# ArduinixMOD.net
KiCad netlist of a schematic drawn in EAGLE
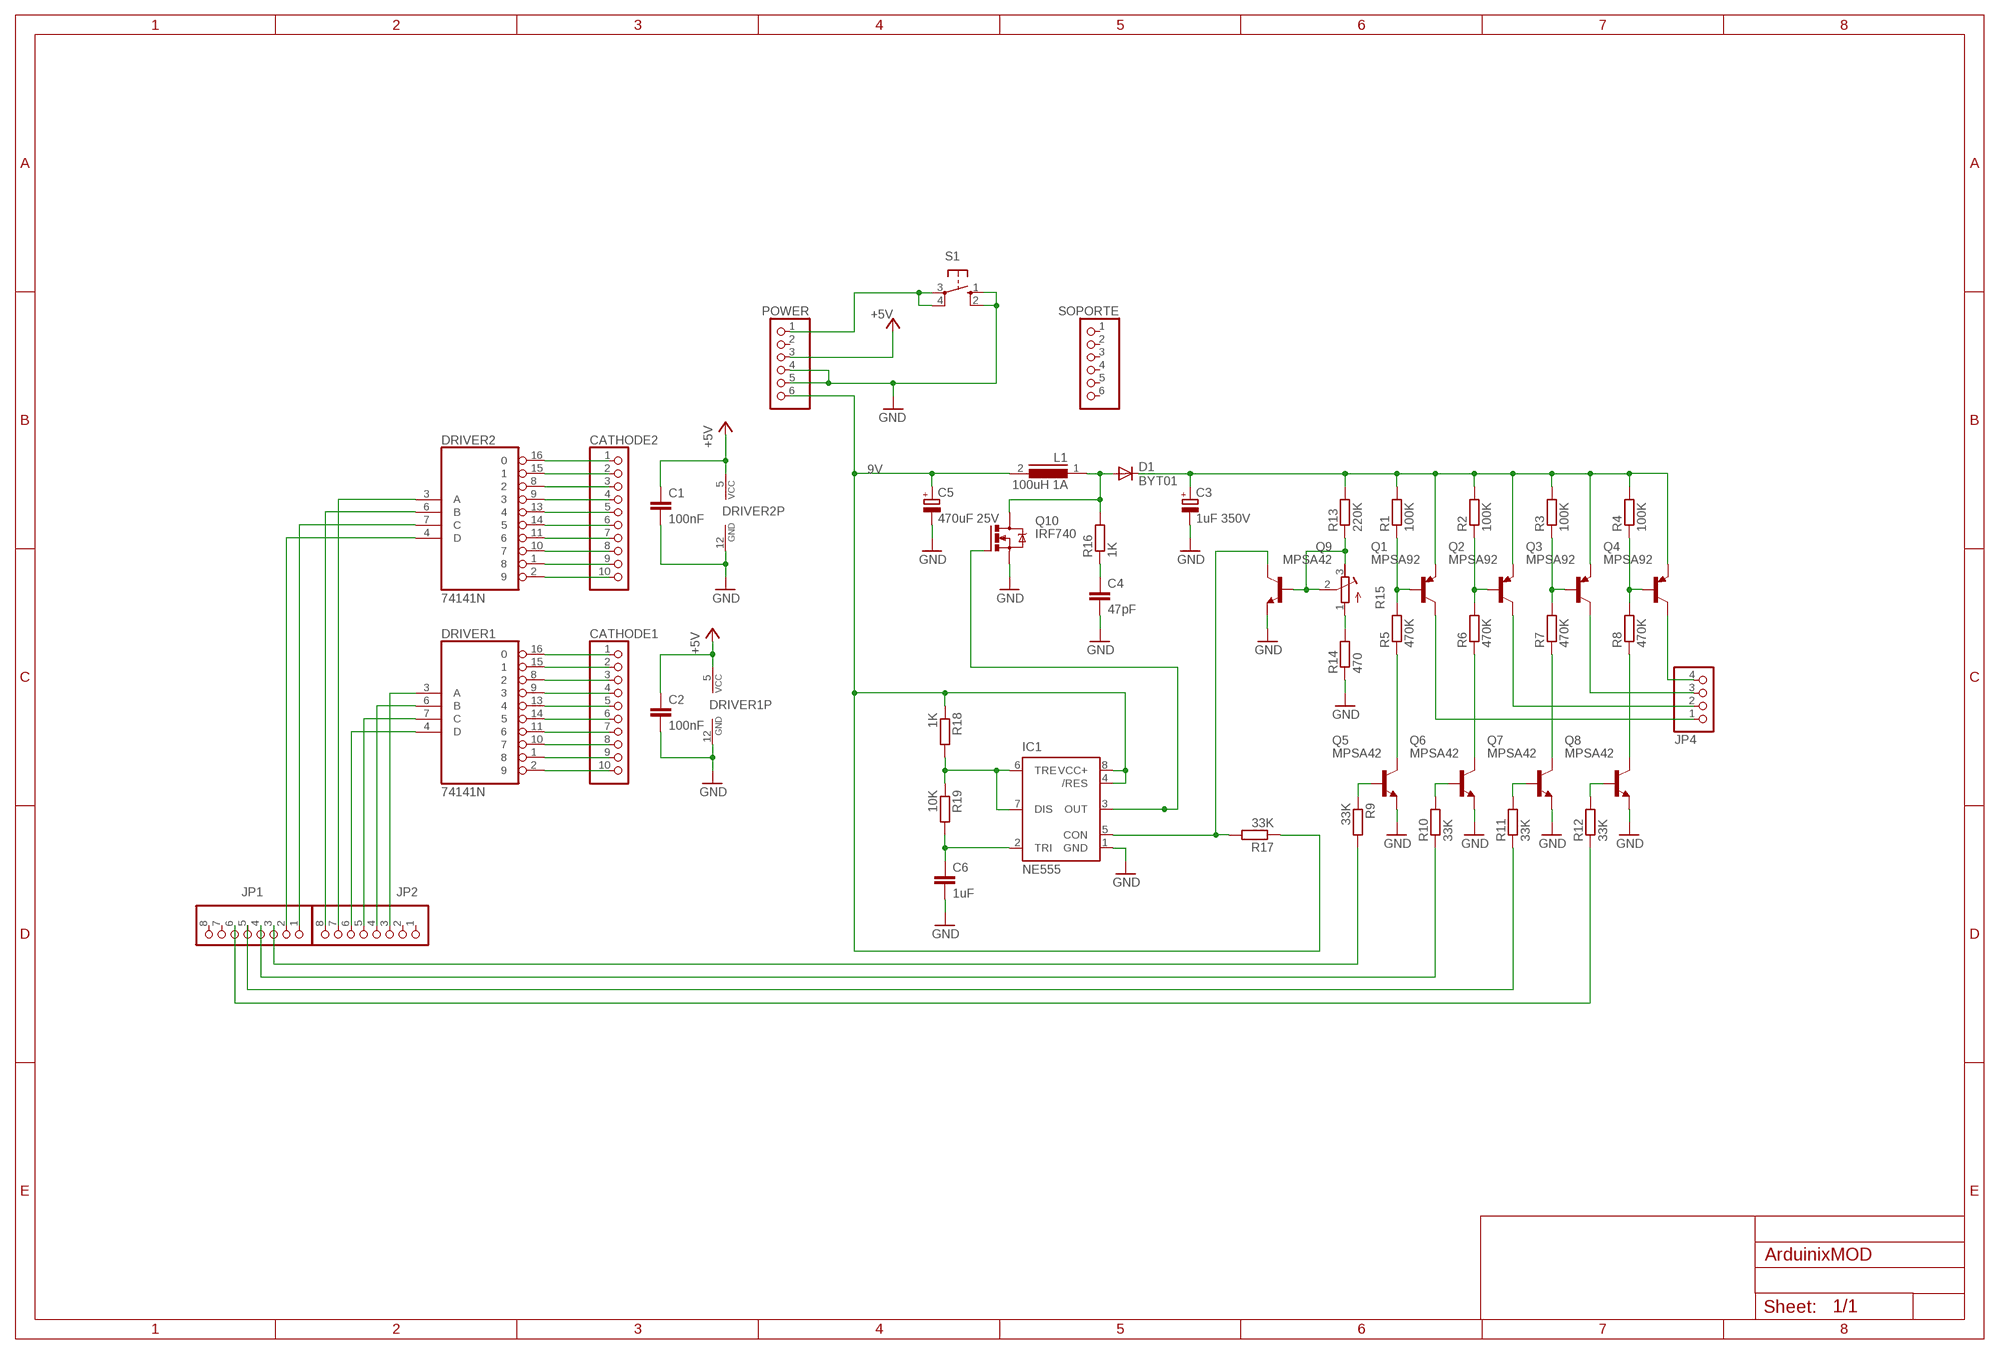
[diagram p0: schematic, sheet 1]

(export (version "E")
  (design (tool "Eeschema 10.0.6"))
  (components
    (comp (ref "C1")
      (value "100nF")
      (footprint "eagle-import:C025-025X050")
      (libsource (lib "eagle-import") (part "C-EU025-025X050"))
    )
    (comp (ref "C2")
      (value "100nF")
      (footprint "eagle-import:C025-025X050")
      (libsource (lib "eagle-import") (part "C-EU025-025X050"))
    )
    (comp (ref "C3")
      (value "1uF 350V")
      (footprint "eagle-import:E2,5-7")
      (libsource (lib "eagle-import") (part "CPOL-EUE2.5-7"))
    )
    (comp (ref "C4")
      (value "47pF")
      (footprint "eagle-import:C025-025X050")
      (libsource (lib "eagle-import") (part "C-EU025-025X050"))
    )
    (comp (ref "C5")
      (value "470uF 25V")
      (footprint "eagle-import:E5-10,5")
      (libsource (lib "eagle-import") (part "CPOL-EUE5-10.5"))
    )
    (comp (ref "C6")
      (value "1uF")
      (footprint "eagle-import:C025-025X050")
      (libsource (lib "eagle-import") (part "C-EU025-025X050"))
    )
    (comp (ref "CATHODE1")
      (value "PINHD-1X10")
      (footprint "eagle-import:1X10")
      (libsource (lib "eagle-import") (part "PINHD-1X10"))
    )
    (comp (ref "CATHODE2")
      (value "PINHD-1X10")
      (footprint "eagle-import:1X10")
      (libsource (lib "eagle-import") (part "PINHD-1X10"))
    )
    (comp (ref "D1")
      (value "BYT01")
      (footprint "eagle-import:F126-10")
      (libsource (lib "eagle-import") (part "BYT01"))
    )
    (comp (ref "DRIVER1")
      (value "74141N")
      (footprint "eagle-import:DIL16")
      (libsource (lib "eagle-import") (part "74141N"))
    )
    (comp (ref "DRIVER2")
      (value "74141N")
      (footprint "eagle-import:DIL16")
      (libsource (lib "eagle-import") (part "74141N"))
    )
    (comp (ref "IC1")
      (value "NE555")
      (footprint "eagle-import:DIL-08")
      (fields (field (name "MF") "Arrow Electronics") (field (name "MPN") "NE555N"))
      (libsource (lib "eagle-import") (part "NE555"))
    )
    (comp (ref "JP1")
      (value "PINHD-1X8")
      (footprint "eagle-import:1X08")
      (libsource (lib "eagle-import") (part "PINHD-1X8"))
    )
    (comp (ref "JP2")
      (value "PINHD-1X8")
      (footprint "eagle-import:1X08")
      (libsource (lib "eagle-import") (part "PINHD-1X8"))
    )
    (comp (ref "JP4")
      (value "PINHD-1X4")
      (footprint "eagle-import:1X04")
      (libsource (lib "eagle-import") (part "PINHD-1X4"))
    )
    (comp (ref "L1")
      (value "100uH 1A")
      (footprint "eagle-import:MESC26")
      (libsource (lib "eagle-import") (part "MESC26"))
    )
    (comp (ref "POWER")
      (value "PINHD-1X6")
      (footprint "eagle-import:1X06")
      (libsource (lib "eagle-import") (part "PINHD-1X6"))
    )
    (comp (ref "Q1")
      (value "MPSA92")
      (footprint "eagle-import:TO92-CBE")
      (libsource (lib "eagle-import") (part "2N4126"))
    )
    (comp (ref "Q2")
      (value "MPSA92")
      (footprint "eagle-import:TO92-CBE")
      (libsource (lib "eagle-import") (part "2N4126"))
    )
    (comp (ref "Q3")
      (value "MPSA92")
      (footprint "eagle-import:TO92-CBE")
      (libsource (lib "eagle-import") (part "2N4126"))
    )
    (comp (ref "Q4")
      (value "MPSA92")
      (footprint "eagle-import:TO92-CBE")
      (libsource (lib "eagle-import") (part "2N4126"))
    )
    (comp (ref "Q5")
      (value "MPSA42")
      (footprint "eagle-import:TO92-EBC")
      (libsource (lib "eagle-import") (part "BC447"))
    )
    (comp (ref "Q6")
      (value "MPSA42")
      (footprint "eagle-import:TO92-EBC")
      (libsource (lib "eagle-import") (part "BC447"))
    )
    (comp (ref "Q7")
      (value "MPSA42")
      (footprint "eagle-import:TO92-EBC")
      (libsource (lib "eagle-import") (part "BC447"))
    )
    (comp (ref "Q8")
      (value "MPSA42")
      (footprint "eagle-import:TO92-EBC")
      (libsource (lib "eagle-import") (part "BC447"))
    )
    (comp (ref "Q9")
      (value "MPSA42")
      (footprint "eagle-import:TO92-EBC")
      (libsource (lib "eagle-import") (part "BC447"))
    )
    (comp (ref "Q10")
      (value "IRF740")
      (footprint "eagle-import:TO220BV")
      (libsource (lib "eagle-import") (part "IRF740"))
    )
    (comp (ref "R1")
      (value "100K")
      (footprint "eagle-import:R1206")
      (libsource (lib "eagle-import") (part "R-EU_R1206"))
    )
    (comp (ref "R2")
      (value "100K")
      (footprint "eagle-import:R1206")
      (libsource (lib "eagle-import") (part "R-EU_R1206"))
    )
    (comp (ref "R3")
      (value "100K")
      (footprint "eagle-import:R1206")
      (libsource (lib "eagle-import") (part "R-EU_R1206"))
    )
    (comp (ref "R4")
      (value "100K")
      (footprint "eagle-import:R1206")
      (libsource (lib "eagle-import") (part "R-EU_R1206"))
    )
    (comp (ref "R5")
      (value "470K")
      (footprint "eagle-import:R1206")
      (libsource (lib "eagle-import") (part "R-EU_R1206"))
    )
    (comp (ref "R6")
      (value "470K")
      (footprint "eagle-import:R1206")
      (libsource (lib "eagle-import") (part "R-EU_R1206"))
    )
    (comp (ref "R7")
      (value "470K")
      (footprint "eagle-import:R1206")
      (libsource (lib "eagle-import") (part "R-EU_R1206"))
    )
    (comp (ref "R8")
      (value "470K")
      (footprint "eagle-import:R1206")
      (libsource (lib "eagle-import") (part "R-EU_R1206"))
    )
    (comp (ref "R9")
      (value "33K")
      (footprint "eagle-import:R1206")
      (libsource (lib "eagle-import") (part "R-EU_R1206"))
    )
    (comp (ref "R10")
      (value "33K")
      (footprint "eagle-import:R1206")
      (libsource (lib "eagle-import") (part "R-EU_R1206"))
    )
    (comp (ref "R11")
      (value "33K")
      (footprint "eagle-import:R1206")
      (libsource (lib "eagle-import") (part "R-EU_R1206"))
    )
    (comp (ref "R12")
      (value "33K")
      (footprint "eagle-import:R1206")
      (libsource (lib "eagle-import") (part "R-EU_R1206"))
    )
    (comp (ref "R13")
      (value "220K")
      (footprint "eagle-import:R1206")
      (libsource (lib "eagle-import") (part "R-EU_R1206"))
    )
    (comp (ref "R14")
      (value "470")
      (footprint "eagle-import:R1206")
      (libsource (lib "eagle-import") (part "R-EU_R1206"))
    )
    (comp (ref "R15")
      (value "R-TRIMM64W")
      (footprint "eagle-import:RTRIM64W")
      (libsource (lib "eagle-import") (part "R-TRIMM64W"))
    )
    (comp (ref "R16")
      (value "1K")
      (footprint "eagle-import:R1206")
      (libsource (lib "eagle-import") (part "R-EU_R1206"))
    )
    (comp (ref "R17")
      (value "33K")
      (footprint "eagle-import:R1206")
      (libsource (lib "eagle-import") (part "R-EU_R1206"))
    )
    (comp (ref "R18")
      (value "1K")
      (footprint "eagle-import:R1206")
      (libsource (lib "eagle-import") (part "R-EU_R1206"))
    )
    (comp (ref "R19")
      (value "10K")
      (footprint "eagle-import:R1206")
      (libsource (lib "eagle-import") (part "R-EU_R1206"))
    )
    (comp (ref "S1")
      (value "10-XX")
      (footprint "eagle-import:B3F-10XX")
      (fields (field (name "MPN") "B3F-1000"))
      (libsource (lib "eagle-import") (part "10-XX"))
    )
    (comp (ref "SOPORTE")
      (value "PINHD-1X6")
      (footprint "eagle-import:1X06")
      (libsource (lib "eagle-import") (part "PINHD-1X6"))
    )
  )
  (nets
    (net (code "1") (name "+5V") (class "Default")
      (node (ref "C1") (pin "1") (pinfunction "1_1") (pintype "passive"))
      (node (ref "C2") (pin "1") (pinfunction "1_1") (pintype "passive"))
      (node (ref "DRIVER1") (pin "5") (pinfunction "VCC_5") (pintype "power_in"))
      (node (ref "DRIVER2") (pin "5") (pinfunction "VCC_5") (pintype "power_in"))
      (node (ref "POWER") (pin "3") (pinfunction "3_3") (pintype "passive"))
    )
    (net (code "2") (name "/9V") (class "Default")
      (node (ref "C5") (pin "+") (pinfunction "+_+") (pintype "passive"))
      (node (ref "IC1") (pin "4") (pinfunction "/RES_4") (pintype "input"))
      (node (ref "IC1") (pin "8") (pinfunction "VCC+_8") (pintype "power_in"))
      (node (ref "L1") (pin "2") (pinfunction "2_2") (pintype "passive"))
      (node (ref "POWER") (pin "6") (pinfunction "6_6") (pintype "passive"))
      (node (ref "R17") (pin "1") (pinfunction "1_1") (pintype "passive"))
      (node (ref "R18") (pin "1") (pinfunction "1_1") (pintype "passive"))
    )
    (net (code "3") (name "GND") (class "Default")
      (node (ref "C1") (pin "2") (pinfunction "2_2") (pintype "passive"))
      (node (ref "C2") (pin "2") (pinfunction "2_2") (pintype "passive"))
      (node (ref "C3") (pin "-") (pinfunction "-_-") (pintype "passive"))
      (node (ref "C4") (pin "2") (pinfunction "2_2") (pintype "passive"))
      (node (ref "C5") (pin "-") (pinfunction "-_-") (pintype "passive"))
      (node (ref "C6") (pin "2") (pinfunction "2_2") (pintype "passive"))
      (node (ref "DRIVER1") (pin "12") (pinfunction "GND_12") (pintype "power_in"))
      (node (ref "DRIVER2") (pin "12") (pinfunction "GND_12") (pintype "power_in"))
      (node (ref "IC1") (pin "1") (pinfunction "GND_1") (pintype "power_in"))
      (node (ref "POWER") (pin "4") (pinfunction "4_4") (pintype "passive"))
      (node (ref "POWER") (pin "5") (pinfunction "5_5") (pintype "passive"))
      (node (ref "Q10") (pin "S") (pinfunction "S_S") (pintype "passive"))
      (node (ref "Q5") (pin "E") (pinfunction "E_E") (pintype "passive"))
      (node (ref "Q6") (pin "E") (pinfunction "E_E") (pintype "passive"))
      (node (ref "Q7") (pin "E") (pinfunction "E_E") (pintype "passive"))
      (node (ref "Q8") (pin "E") (pinfunction "E_E") (pintype "passive"))
      (node (ref "Q9") (pin "E") (pinfunction "E_E") (pintype "passive"))
      (node (ref "R14") (pin "1") (pinfunction "1_1") (pintype "passive"))
      (node (ref "S1") (pin "1") (pinfunction "S_1") (pintype "passive"))
      (node (ref "S1") (pin "2") (pinfunction "S1_2") (pintype "passive"))
    )
    (net (code "4") (name "Net-(C3-Pad+)") (class "Default")
      (node (ref "C3") (pin "+") (pinfunction "+_+") (pintype "passive"))
      (node (ref "D1") (pin "C") (pinfunction "C_C") (pintype "passive"))
      (node (ref "Q1") (pin "E") (pinfunction "E_E") (pintype "passive"))
      (node (ref "Q2") (pin "E") (pinfunction "E_E") (pintype "passive"))
      (node (ref "Q3") (pin "E") (pinfunction "E_E") (pintype "passive"))
      (node (ref "Q4") (pin "E") (pinfunction "E_E") (pintype "passive"))
      (node (ref "R1") (pin "2") (pinfunction "2_2") (pintype "passive"))
      (node (ref "R13") (pin "2") (pinfunction "2_2") (pintype "passive"))
      (node (ref "R2") (pin "2") (pinfunction "2_2") (pintype "passive"))
      (node (ref "R3") (pin "2") (pinfunction "2_2") (pintype "passive"))
      (node (ref "R4") (pin "2") (pinfunction "2_2") (pintype "passive"))
    )
    (net (code "5") (name "Net-(C4-Pad1)") (class "Default")
      (node (ref "C4") (pin "1") (pinfunction "1_1") (pintype "passive"))
      (node (ref "R16") (pin "1") (pinfunction "1_1") (pintype "passive"))
    )
    (net (code "6") (name "Net-(D1-PadA)") (class "Default")
      (node (ref "D1") (pin "A") (pinfunction "A_A") (pintype "passive"))
      (node (ref "L1") (pin "1") (pinfunction "1_1") (pintype "passive"))
      (node (ref "Q10") (pin "D") (pinfunction "D_D") (pintype "passive"))
      (node (ref "R16") (pin "2") (pinfunction "2_2") (pintype "passive"))
    )
    (net (code "7") (name "Net-(DRIVER1A-0)") (class "Default")
      (node (ref "CATHODE1") (pin "1") (pinfunction "1_1") (pintype "passive"))
      (node (ref "DRIVER1") (pin "16") (pinfunction "0_16") (pintype "open_collector"))
    )
    (net (code "8") (name "Net-(DRIVER1A-1)") (class "Default")
      (node (ref "CATHODE1") (pin "2") (pinfunction "2_2") (pintype "passive"))
      (node (ref "DRIVER1") (pin "15") (pinfunction "1_15") (pintype "open_collector"))
    )
    (net (code "9") (name "Net-(DRIVER1A-2)") (class "Default")
      (node (ref "CATHODE1") (pin "3") (pinfunction "3_3") (pintype "passive"))
      (node (ref "DRIVER1") (pin "8") (pinfunction "2_8") (pintype "open_collector"))
    )
    (net (code "10") (name "Net-(DRIVER1A-3)") (class "Default")
      (node (ref "CATHODE1") (pin "4") (pinfunction "4_4") (pintype "passive"))
      (node (ref "DRIVER1") (pin "9") (pinfunction "3_9") (pintype "open_collector"))
    )
    (net (code "11") (name "Net-(DRIVER1A-4)") (class "Default")
      (node (ref "CATHODE1") (pin "5") (pinfunction "5_5") (pintype "passive"))
      (node (ref "DRIVER1") (pin "13") (pinfunction "4_13") (pintype "open_collector"))
    )
    (net (code "12") (name "Net-(DRIVER1A-5)") (class "Default")
      (node (ref "CATHODE1") (pin "6") (pinfunction "6_6") (pintype "passive"))
      (node (ref "DRIVER1") (pin "14") (pinfunction "5_14") (pintype "open_collector"))
    )
    (net (code "13") (name "Net-(DRIVER1A-6)") (class "Default")
      (node (ref "CATHODE1") (pin "7") (pinfunction "7_7") (pintype "passive"))
      (node (ref "DRIVER1") (pin "11") (pinfunction "6_11") (pintype "open_collector"))
    )
    (net (code "14") (name "Net-(DRIVER1A-7)") (class "Default")
      (node (ref "CATHODE1") (pin "8") (pinfunction "8_8") (pintype "passive"))
      (node (ref "DRIVER1") (pin "10") (pinfunction "7_10") (pintype "open_collector"))
    )
    (net (code "15") (name "Net-(DRIVER1A-8)") (class "Default")
      (node (ref "CATHODE1") (pin "9") (pinfunction "9_9") (pintype "passive"))
      (node (ref "DRIVER1") (pin "1") (pinfunction "8_1") (pintype "open_collector"))
    )
    (net (code "16") (name "Net-(DRIVER1A-9)") (class "Default")
      (node (ref "CATHODE1") (pin "10") (pinfunction "10_10") (pintype "passive"))
      (node (ref "DRIVER1") (pin "2") (pinfunction "9_2") (pintype "open_collector"))
    )
    (net (code "17") (name "Net-(DRIVER1A-A)") (class "Default")
      (node (ref "DRIVER1") (pin "3") (pinfunction "A_3") (pintype "input"))
      (node (ref "JP2") (pin "3") (pinfunction "3_3") (pintype "passive"))
    )
    (net (code "18") (name "Net-(DRIVER1A-B)") (class "Default")
      (node (ref "DRIVER1") (pin "6") (pinfunction "B_6") (pintype "input"))
      (node (ref "JP2") (pin "4") (pinfunction "4_4") (pintype "passive"))
    )
    (net (code "19") (name "Net-(DRIVER1A-C)") (class "Default")
      (node (ref "DRIVER1") (pin "7") (pinfunction "C_7") (pintype "input"))
      (node (ref "JP2") (pin "5") (pinfunction "5_5") (pintype "passive"))
    )
    (net (code "20") (name "Net-(DRIVER1A-D)") (class "Default")
      (node (ref "DRIVER1") (pin "4") (pinfunction "D_4") (pintype "input"))
      (node (ref "JP2") (pin "6") (pinfunction "6_6") (pintype "passive"))
    )
    (net (code "21") (name "Net-(DRIVER2A-0)") (class "Default")
      (node (ref "CATHODE2") (pin "1") (pinfunction "1_1") (pintype "passive"))
      (node (ref "DRIVER2") (pin "16") (pinfunction "0_16") (pintype "open_collector"))
    )
    (net (code "22") (name "Net-(DRIVER2A-1)") (class "Default")
      (node (ref "CATHODE2") (pin "2") (pinfunction "2_2") (pintype "passive"))
      (node (ref "DRIVER2") (pin "15") (pinfunction "1_15") (pintype "open_collector"))
    )
    (net (code "23") (name "Net-(DRIVER2A-2)") (class "Default")
      (node (ref "CATHODE2") (pin "3") (pinfunction "3_3") (pintype "passive"))
      (node (ref "DRIVER2") (pin "8") (pinfunction "2_8") (pintype "open_collector"))
    )
    (net (code "24") (name "Net-(DRIVER2A-3)") (class "Default")
      (node (ref "CATHODE2") (pin "4") (pinfunction "4_4") (pintype "passive"))
      (node (ref "DRIVER2") (pin "9") (pinfunction "3_9") (pintype "open_collector"))
    )
    (net (code "25") (name "Net-(DRIVER2A-4)") (class "Default")
      (node (ref "CATHODE2") (pin "5") (pinfunction "5_5") (pintype "passive"))
      (node (ref "DRIVER2") (pin "13") (pinfunction "4_13") (pintype "open_collector"))
    )
    (net (code "26") (name "Net-(DRIVER2A-5)") (class "Default")
      (node (ref "CATHODE2") (pin "6") (pinfunction "6_6") (pintype "passive"))
      (node (ref "DRIVER2") (pin "14") (pinfunction "5_14") (pintype "open_collector"))
    )
    (net (code "27") (name "Net-(DRIVER2A-6)") (class "Default")
      (node (ref "CATHODE2") (pin "7") (pinfunction "7_7") (pintype "passive"))
      (node (ref "DRIVER2") (pin "11") (pinfunction "6_11") (pintype "open_collector"))
    )
    (net (code "28") (name "Net-(DRIVER2A-7)") (class "Default")
      (node (ref "CATHODE2") (pin "8") (pinfunction "8_8") (pintype "passive"))
      (node (ref "DRIVER2") (pin "10") (pinfunction "7_10") (pintype "open_collector"))
    )
    (net (code "29") (name "Net-(DRIVER2A-8)") (class "Default")
      (node (ref "CATHODE2") (pin "9") (pinfunction "9_9") (pintype "passive"))
      (node (ref "DRIVER2") (pin "1") (pinfunction "8_1") (pintype "open_collector"))
    )
    (net (code "30") (name "Net-(DRIVER2A-9)") (class "Default")
      (node (ref "CATHODE2") (pin "10") (pinfunction "10_10") (pintype "passive"))
      (node (ref "DRIVER2") (pin "2") (pinfunction "9_2") (pintype "open_collector"))
    )
    (net (code "31") (name "Net-(DRIVER2A-A)") (class "Default")
      (node (ref "DRIVER2") (pin "3") (pinfunction "A_3") (pintype "input"))
      (node (ref "JP2") (pin "7") (pinfunction "7_7") (pintype "passive"))
    )
    (net (code "32") (name "Net-(DRIVER2A-B)") (class "Default")
      (node (ref "DRIVER2") (pin "6") (pinfunction "B_6") (pintype "input"))
      (node (ref "JP2") (pin "8") (pinfunction "8_8") (pintype "passive"))
    )
    (net (code "33") (name "Net-(DRIVER2A-C)") (class "Default")
      (node (ref "DRIVER2") (pin "7") (pinfunction "C_7") (pintype "input"))
      (node (ref "JP1") (pin "1") (pinfunction "1_1") (pintype "passive"))
    )
    (net (code "34") (name "Net-(DRIVER2A-D)") (class "Default")
      (node (ref "DRIVER2") (pin "4") (pinfunction "D_4") (pintype "input"))
      (node (ref "JP1") (pin "2") (pinfunction "2_2") (pintype "passive"))
    )
    (net (code "35") (name "Net-(IC1-CON)") (class "Default")
      (node (ref "IC1") (pin "5") (pinfunction "CON_5") (pintype "input"))
      (node (ref "Q9") (pin "C") (pinfunction "C_C") (pintype "passive"))
      (node (ref "R17") (pin "2") (pinfunction "2_2") (pintype "passive"))
    )
    (net (code "36") (name "Net-(IC1-DIS)") (class "Default")
      (node (ref "IC1") (pin "6") (pinfunction "TRE_6") (pintype "input"))
      (node (ref "IC1") (pin "7") (pinfunction "DIS_7") (pintype "input"))
      (node (ref "R18") (pin "2") (pinfunction "2_2") (pintype "passive"))
      (node (ref "R19") (pin "1") (pinfunction "1_1") (pintype "passive"))
    )
    (net (code "37") (name "Net-(IC1-OUT)") (class "Default")
      (node (ref "IC1") (pin "3") (pinfunction "OUT_3") (pintype "output"))
      (node (ref "Q10") (pin "G") (pinfunction "G_G") (pintype "passive"))
    )
    (net (code "38") (name "Net-(IC1-TRI)") (class "Default")
      (node (ref "C6") (pin "1") (pinfunction "1_1") (pintype "passive"))
      (node (ref "IC1") (pin "2") (pinfunction "TRI_2") (pintype "input"))
      (node (ref "R19") (pin "2") (pinfunction "2_2") (pintype "passive"))
    )
    (net (code "39") (name "Net-(JP1-Pad3)") (class "Default")
      (node (ref "JP1") (pin "3") (pinfunction "3_3") (pintype "passive"))
      (node (ref "R9") (pin "2") (pinfunction "2_2") (pintype "passive"))
    )
    (net (code "40") (name "Net-(JP1-Pad4)") (class "Default")
      (node (ref "JP1") (pin "4") (pinfunction "4_4") (pintype "passive"))
      (node (ref "R10") (pin "1") (pinfunction "1_1") (pintype "passive"))
    )
    (net (code "41") (name "Net-(JP1-Pad5)") (class "Default")
      (node (ref "JP1") (pin "5") (pinfunction "5_5") (pintype "passive"))
      (node (ref "R11") (pin "1") (pinfunction "1_1") (pintype "passive"))
    )
    (net (code "42") (name "Net-(JP1-Pad6)") (class "Default")
      (node (ref "JP1") (pin "6") (pinfunction "6_6") (pintype "passive"))
      (node (ref "R12") (pin "1") (pinfunction "1_1") (pintype "passive"))
    )
    (net (code "43") (name "Net-(JP4-Pad1)") (class "Default")
      (node (ref "JP4") (pin "1") (pinfunction "1_1") (pintype "passive"))
      (node (ref "Q1") (pin "C") (pinfunction "C_C") (pintype "passive"))
    )
    (net (code "44") (name "Net-(JP4-Pad2)") (class "Default")
      (node (ref "JP4") (pin "2") (pinfunction "2_2") (pintype "passive"))
      (node (ref "Q2") (pin "C") (pinfunction "C_C") (pintype "passive"))
    )
    (net (code "45") (name "Net-(JP4-Pad3)") (class "Default")
      (node (ref "JP4") (pin "3") (pinfunction "3_3") (pintype "passive"))
      (node (ref "Q3") (pin "C") (pinfunction "C_C") (pintype "passive"))
    )
    (net (code "46") (name "Net-(JP4-Pad4)") (class "Default")
      (node (ref "JP4") (pin "4") (pinfunction "4_4") (pintype "passive"))
      (node (ref "Q4") (pin "C") (pinfunction "C_C") (pintype "passive"))
    )
    (net (code "47") (name "Net-(Q1-PadB)") (class "Default")
      (node (ref "Q1") (pin "B") (pinfunction "B_B") (pintype "passive"))
      (node (ref "R1") (pin "1") (pinfunction "1_1") (pintype "passive"))
      (node (ref "R5") (pin "2") (pinfunction "2_2") (pintype "passive"))
    )
    (net (code "48") (name "Net-(Q2-PadB)") (class "Default")
      (node (ref "Q2") (pin "B") (pinfunction "B_B") (pintype "passive"))
      (node (ref "R2") (pin "1") (pinfunction "1_1") (pintype "passive"))
      (node (ref "R6") (pin "2") (pinfunction "2_2") (pintype "passive"))
    )
    (net (code "49") (name "Net-(Q3-PadB)") (class "Default")
      (node (ref "Q3") (pin "B") (pinfunction "B_B") (pintype "passive"))
      (node (ref "R3") (pin "1") (pinfunction "1_1") (pintype "passive"))
      (node (ref "R7") (pin "2") (pinfunction "2_2") (pintype "passive"))
    )
    (net (code "50") (name "Net-(Q4-PadB)") (class "Default")
      (node (ref "Q4") (pin "B") (pinfunction "B_B") (pintype "passive"))
      (node (ref "R4") (pin "1") (pinfunction "1_1") (pintype "passive"))
      (node (ref "R8") (pin "2") (pinfunction "2_2") (pintype "passive"))
    )
    (net (code "51") (name "Net-(Q5-PadB)") (class "Default")
      (node (ref "Q5") (pin "B") (pinfunction "B_B") (pintype "passive"))
      (node (ref "R9") (pin "1") (pinfunction "1_1") (pintype "passive"))
    )
    (net (code "52") (name "Net-(Q5-PadC)") (class "Default")
      (node (ref "Q5") (pin "C") (pinfunction "C_C") (pintype "passive"))
      (node (ref "R5") (pin "1") (pinfunction "1_1") (pintype "passive"))
    )
    (net (code "53") (name "Net-(Q6-PadB)") (class "Default")
      (node (ref "Q6") (pin "B") (pinfunction "B_B") (pintype "passive"))
      (node (ref "R10") (pin "2") (pinfunction "2_2") (pintype "passive"))
    )
    (net (code "54") (name "Net-(Q6-PadC)") (class "Default")
      (node (ref "Q6") (pin "C") (pinfunction "C_C") (pintype "passive"))
      (node (ref "R6") (pin "1") (pinfunction "1_1") (pintype "passive"))
    )
    (net (code "55") (name "Net-(Q7-PadB)") (class "Default")
      (node (ref "Q7") (pin "B") (pinfunction "B_B") (pintype "passive"))
      (node (ref "R11") (pin "2") (pinfunction "2_2") (pintype "passive"))
    )
    (net (code "56") (name "Net-(Q7-PadC)") (class "Default")
      (node (ref "Q7") (pin "C") (pinfunction "C_C") (pintype "passive"))
      (node (ref "R7") (pin "1") (pinfunction "1_1") (pintype "passive"))
    )
    (net (code "57") (name "Net-(Q8-PadB)") (class "Default")
      (node (ref "Q8") (pin "B") (pinfunction "B_B") (pintype "passive"))
      (node (ref "R12") (pin "2") (pinfunction "2_2") (pintype "passive"))
    )
    (net (code "58") (name "Net-(Q8-PadC)") (class "Default")
      (node (ref "Q8") (pin "C") (pinfunction "C_C") (pintype "passive"))
      (node (ref "R8") (pin "1") (pinfunction "1_1") (pintype "passive"))
    )
    (net (code "59") (name "Net-(R15-A)") (class "Default")
      (node (ref "R14") (pin "2") (pinfunction "2_2") (pintype "passive"))
      (node (ref "R15") (pin "1") (pinfunction "A_1") (pintype "passive"))
    )
    (net (code "60") (name "Net-(R15-E)") (class "Default")
      (node (ref "Q9") (pin "B") (pinfunction "B_B") (pintype "passive"))
      (node (ref "R13") (pin "1") (pinfunction "1_1") (pintype "passive"))
      (node (ref "R15") (pin "2") (pinfunction "S_2") (pintype "passive"))
      (node (ref "R15") (pin "3") (pinfunction "E_3") (pintype "passive"))
    )
    (net (code "61") (name "Net-(S1-P)") (class "Default")
      (node (ref "POWER") (pin "1") (pinfunction "1_1") (pintype "passive"))
      (node (ref "S1") (pin "3") (pinfunction "P_3") (pintype "passive"))
      (node (ref "S1") (pin "4") (pinfunction "P1_4") (pintype "passive"))
    )
    (net (code "62") (name "unconnected-(JP1-Pad7)") (class "Default")
      (node (ref "JP1") (pin "7") (pinfunction "7_7") (pintype "passive"))
    )
    (net (code "63") (name "unconnected-(JP1-Pad8)") (class "Default")
      (node (ref "JP1") (pin "8") (pinfunction "8_8") (pintype "passive"))
    )
    (net (code "64") (name "unconnected-(JP2-Pad1)") (class "Default")
      (node (ref "JP2") (pin "1") (pinfunction "1_1") (pintype "passive"))
    )
    (net (code "65") (name "unconnected-(JP2-Pad2)") (class "Default")
      (node (ref "JP2") (pin "2") (pinfunction "2_2") (pintype "passive"))
    )
    (net (code "66") (name "unconnected-(POWER-Pad2)") (class "Default")
      (node (ref "POWER") (pin "2") (pinfunction "2_2") (pintype "passive"))
    )
    (net (code "67") (name "unconnected-(SOPORTE-Pad1)") (class "Default")
      (node (ref "SOPORTE") (pin "1") (pinfunction "1_1") (pintype "passive"))
    )
    (net (code "68") (name "unconnected-(SOPORTE-Pad2)") (class "Default")
      (node (ref "SOPORTE") (pin "2") (pinfunction "2_2") (pintype "passive"))
    )
    (net (code "69") (name "unconnected-(SOPORTE-Pad3)") (class "Default")
      (node (ref "SOPORTE") (pin "3") (pinfunction "3_3") (pintype "passive"))
    )
    (net (code "70") (name "unconnected-(SOPORTE-Pad4)") (class "Default")
      (node (ref "SOPORTE") (pin "4") (pinfunction "4_4") (pintype "passive"))
    )
    (net (code "71") (name "unconnected-(SOPORTE-Pad5)") (class "Default")
      (node (ref "SOPORTE") (pin "5") (pinfunction "5_5") (pintype "passive"))
    )
    (net (code "72") (name "unconnected-(SOPORTE-Pad6)") (class "Default")
      (node (ref "SOPORTE") (pin "6") (pinfunction "6_6") (pintype "passive"))
    )
  )
)
